# MAGI_sCore-MBH.net
KiCad netlist of a schematic drawn in Altium Designer
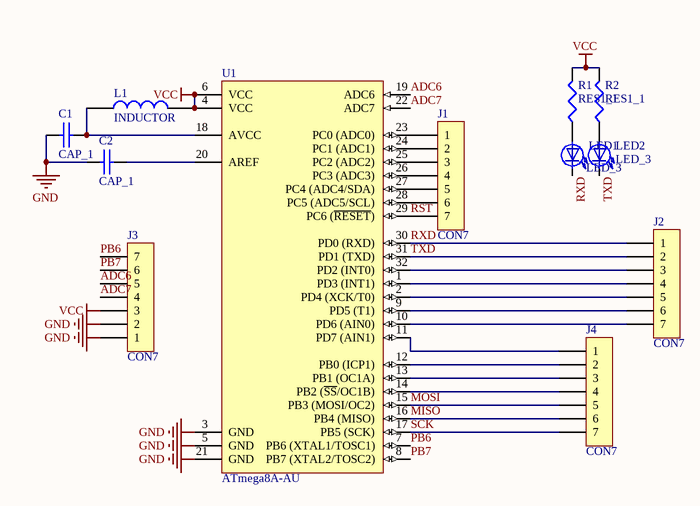
[diagram p0: MAGI'sCore-MBH.SchDoc]

(export (version "E")
  (design (tool "Eeschema 10.0.6"))
  (components
    (comp (ref "C1")
      (value "CAP_1")
      (footprint "1210")
      (description "Capacitor")
      (libsource (lib "电容器") (part "CAP_1"))
    )
    (comp (ref "C2")
      (value "CAP_1")
      (footprint "1210")
      (description "Capacitor")
      (libsource (lib "电容器") (part "CAP_1"))
    )
    (comp (ref "J1")
      (value "CON7")
      (footprint "CON7")
      (description "Connector")
      (libsource (lib "") (part "CON7_1"))
    )
    (comp (ref "J2")
      (value "CON7")
      (footprint "CON7")
      (description "Connector")
      (libsource (lib "") (part "CON7_1"))
    )
    (comp (ref "J3")
      (value "CON7")
      (footprint "CON7")
      (description "Connector")
      (libsource (lib "CON系列") (part "CON7"))
    )
    (comp (ref "J4")
      (value "CON7")
      (footprint "CON7")
      (description "Connector")
      (libsource (lib "") (part "CON7_1"))
    )
    (comp (ref "L1") (value "INDUCTOR") (footprint "22uh") (libsource (lib "汇总") (part "INDUCTOR")))
    (comp (ref "LED1") (value "LED_3") (footprint "0805") (libsource (lib "二极管") (part "LED_3")))
    (comp (ref "LED2") (value "LED_3") (footprint "0805") (libsource (lib "二极管") (part "LED_3")))
    (comp (ref "R1") (value "RES1_1") (footprint "0805") (libsource (lib "电阻器") (part "RES1_1")))
    (comp (ref "R2") (value "RES1_1") (footprint "0805") (libsource (lib "电阻器") (part "RES1_1")))
    (comp (ref "U1")
      (value "ATmega8A-AU")
      (footprint "32A_N")
      (fields (field (name "PUBLISHER") "Altium Limited"))
      (libsource (lib "Atmel Microcontroller 8-Bit megaAVR") (part "ATmega8A-AU"))
    )
  )
  (nets
    (net (code "1") (name "/ADC6") (class "Default")
      (node (ref "J3") (pin "5") (pinfunction "5_5") (pintype "passive"))
      (node (ref "U1") (pin "19") (pinfunction "ADC6_19") (pintype "input"))
    )
    (net (code "2") (name "/ADC7") (class "Default")
      (node (ref "J3") (pin "4") (pinfunction "4_4") (pintype "passive"))
      (node (ref "U1") (pin "22") (pinfunction "ADC7_22") (pintype "input"))
    )
    (net (code "3") (name "/MISO") (class "Default")
      (node (ref "J4") (pin "6") (pinfunction "6_6") (pintype "passive"))
      (node (ref "U1") (pin "16") (pinfunction "PB4_(MISO)_16") (pintype "bidirectional"))
    )
    (net (code "4") (name "/MOSI") (class "Default")
      (node (ref "J4") (pin "5") (pinfunction "5_5") (pintype "passive"))
      (node (ref "U1") (pin "15") (pinfunction "PB3_(MOSI/OC2)_15") (pintype "bidirectional"))
    )
    (net (code "5") (name "/PB6") (class "Default")
      (node (ref "J3") (pin "7") (pinfunction "7_7") (pintype "passive"))
      (node (ref "U1") (pin "7") (pinfunction "PB6_(XTAL1/TOSC1)_7") (pintype "bidirectional"))
    )
    (net (code "6") (name "/PB7") (class "Default")
      (node (ref "J3") (pin "6") (pinfunction "6_6") (pintype "passive"))
      (node (ref "U1") (pin "8") (pinfunction "PB7_(XTAL2/TOSC2)_8") (pintype "bidirectional"))
    )
    (net (code "7") (name "/RST") (class "Default")
      (node (ref "J1") (pin "7") (pinfunction "7_7") (pintype "passive"))
      (node (ref "U1") (pin "29") (pinfunction "PC6_(~{RESET})_29") (pintype "bidirectional"))
    )
    (net (code "8") (name "/RXD") (class "Default")
      (node (ref "J2") (pin "1") (pinfunction "1_1") (pintype "passive"))
      (node (ref "LED1") (pin "2") (pinfunction "K_2") (pintype "passive"))
      (node (ref "U1") (pin "30") (pinfunction "PD0_(RXD)_30") (pintype "bidirectional"))
    )
    (net (code "9") (name "/SCK") (class "Default")
      (node (ref "J4") (pin "7") (pinfunction "7_7") (pintype "passive"))
      (node (ref "U1") (pin "17") (pinfunction "PB5_(SCK)_17") (pintype "bidirectional"))
    )
    (net (code "10") (name "/TXD") (class "Default")
      (node (ref "J2") (pin "2") (pinfunction "2_2") (pintype "passive"))
      (node (ref "LED2") (pin "2") (pinfunction "K_2") (pintype "passive"))
      (node (ref "U1") (pin "31") (pinfunction "PD1_(TXD)_31") (pintype "bidirectional"))
    )
    (net (code "11") (name "GND") (class "Default")
      (node (ref "C1") (pin "1") (pinfunction "1_1") (pintype "passive"))
      (node (ref "C2") (pin "1") (pinfunction "1_1") (pintype "passive"))
      (node (ref "J3") (pin "1") (pinfunction "1_1") (pintype "passive"))
      (node (ref "J3") (pin "2") (pinfunction "2_2") (pintype "passive"))
      (node (ref "U1") (pin "21") (pinfunction "GND_21") (pintype "power_in"))
      (node (ref "U1") (pin "3") (pinfunction "GND_3") (pintype "power_in"))
      (node (ref "U1") (pin "5") (pinfunction "GND_5") (pintype "power_in"))
    )
    (net (code "12") (name "Net-(LED1-A)") (class "Default")
      (node (ref "LED1") (pin "1") (pinfunction "A_1") (pintype "passive"))
      (node (ref "R1") (pin "1") (pinfunction "1_1") (pintype "passive"))
    )
    (net (code "13") (name "Net-(LED2-A)") (class "Default")
      (node (ref "LED2") (pin "1") (pinfunction "A_1") (pintype "passive"))
      (node (ref "R2") (pin "1") (pinfunction "1_1") (pintype "passive"))
    )
    (net (code "14") (name "Net-(U1-AREF)") (class "Default")
      (node (ref "C2") (pin "2") (pinfunction "2_2") (pintype "passive"))
      (node (ref "U1") (pin "20") (pinfunction "AREF_20") (pintype "power_in"))
    )
    (net (code "15") (name "Net-(U1-AVCC)") (class "Default")
      (node (ref "C1") (pin "2") (pinfunction "2_2") (pintype "passive"))
      (node (ref "L1") (pin "1") (pinfunction "1_1") (pintype "passive"))
      (node (ref "U1") (pin "18") (pinfunction "AVCC_18") (pintype "power_in"))
    )
    (net (code "16") (name "Net-(U1-PB0_(ICP1))") (class "Default")
      (node (ref "J4") (pin "2") (pinfunction "2_2") (pintype "passive"))
      (node (ref "U1") (pin "12") (pinfunction "PB0_(ICP1)_12") (pintype "bidirectional"))
    )
    (net (code "17") (name "Net-(U1-PB1_(OC1A))") (class "Default")
      (node (ref "J4") (pin "3") (pinfunction "3_3") (pintype "passive"))
      (node (ref "U1") (pin "13") (pinfunction "PB1_(OC1A)_13") (pintype "bidirectional"))
    )
    (net (code "18") (name "Net-(U1-PB2_(~{SS}{slash}OC1B))") (class "Default")
      (node (ref "J4") (pin "4") (pinfunction "4_4") (pintype "passive"))
      (node (ref "U1") (pin "14") (pinfunction "PB2_(~{SS}/OC1B)_14") (pintype "bidirectional"))
    )
    (net (code "19") (name "Net-(U1-PC0_(ADC0))") (class "Default")
      (node (ref "J1") (pin "1") (pinfunction "1_1") (pintype "passive"))
      (node (ref "U1") (pin "23") (pinfunction "PC0_(ADC0)_23") (pintype "bidirectional"))
    )
    (net (code "20") (name "Net-(U1-PC1_(ADC1))") (class "Default")
      (node (ref "J1") (pin "2") (pinfunction "2_2") (pintype "passive"))
      (node (ref "U1") (pin "24") (pinfunction "PC1_(ADC1)_24") (pintype "bidirectional"))
    )
    (net (code "21") (name "Net-(U1-PC2_(ADC2))") (class "Default")
      (node (ref "J1") (pin "3") (pinfunction "3_3") (pintype "passive"))
      (node (ref "U1") (pin "25") (pinfunction "PC2_(ADC2)_25") (pintype "bidirectional"))
    )
    (net (code "22") (name "Net-(U1-PC3_(ADC3))") (class "Default")
      (node (ref "J1") (pin "4") (pinfunction "4_4") (pintype "passive"))
      (node (ref "U1") (pin "26") (pinfunction "PC3_(ADC3)_26") (pintype "bidirectional"))
    )
    (net (code "23") (name "Net-(U1-PC4_(ADC4{slash}SDA))") (class "Default")
      (node (ref "J1") (pin "5") (pinfunction "5_5") (pintype "passive"))
      (node (ref "U1") (pin "27") (pinfunction "PC4_(ADC4/SDA)_27") (pintype "bidirectional"))
    )
    (net (code "24") (name "Net-(U1-PC5_(ADC5{slash}SCL))") (class "Default")
      (node (ref "J1") (pin "6") (pinfunction "6_6") (pintype "passive"))
      (node (ref "U1") (pin "28") (pinfunction "PC5_(ADC5/SCL)_28") (pintype "bidirectional"))
    )
    (net (code "25") (name "Net-(U1-PD2_(INT0))") (class "Default")
      (node (ref "J2") (pin "3") (pinfunction "3_3") (pintype "passive"))
      (node (ref "U1") (pin "32") (pinfunction "PD2_(INT0)_32") (pintype "bidirectional"))
    )
    (net (code "26") (name "Net-(U1-PD3_(INT1))") (class "Default")
      (node (ref "J2") (pin "4") (pinfunction "4_4") (pintype "passive"))
      (node (ref "U1") (pin "1") (pinfunction "PD3_(INT1)_1") (pintype "bidirectional"))
    )
    (net (code "27") (name "Net-(U1-PD4_(XCK{slash}T0))") (class "Default")
      (node (ref "J2") (pin "5") (pinfunction "5_5") (pintype "passive"))
      (node (ref "U1") (pin "2") (pinfunction "PD4_(XCK/T0)_2") (pintype "bidirectional"))
    )
    (net (code "28") (name "Net-(U1-PD5_(T1))") (class "Default")
      (node (ref "J2") (pin "6") (pinfunction "6_6") (pintype "passive"))
      (node (ref "U1") (pin "9") (pinfunction "PD5_(T1)_9") (pintype "bidirectional"))
    )
    (net (code "29") (name "Net-(U1-PD6_(AIN0))") (class "Default")
      (node (ref "J2") (pin "7") (pinfunction "7_7") (pintype "passive"))
      (node (ref "U1") (pin "10") (pinfunction "PD6_(AIN0)_10") (pintype "bidirectional"))
    )
    (net (code "30") (name "Net-(U1-PD7_(AIN1))") (class "Default")
      (node (ref "J4") (pin "1") (pinfunction "1_1") (pintype "passive"))
      (node (ref "U1") (pin "11") (pinfunction "PD7_(AIN1)_11") (pintype "bidirectional"))
    )
    (net (code "31") (name "VCC") (class "Default")
      (node (ref "J3") (pin "3") (pinfunction "3_3") (pintype "passive"))
      (node (ref "L1") (pin "2") (pinfunction "2_2") (pintype "passive"))
      (node (ref "R1") (pin "2") (pinfunction "2_2") (pintype "passive"))
      (node (ref "R2") (pin "2") (pinfunction "2_2") (pintype "passive"))
      (node (ref "U1") (pin "4") (pinfunction "VCC_4") (pintype "power_in"))
      (node (ref "U1") (pin "6") (pinfunction "VCC_6") (pintype "power_in"))
    )
  )
)
